# Arduino_FPGA_Top-Level_Interface.net
KiCad netlist of a schematic drawn in Altium Designer
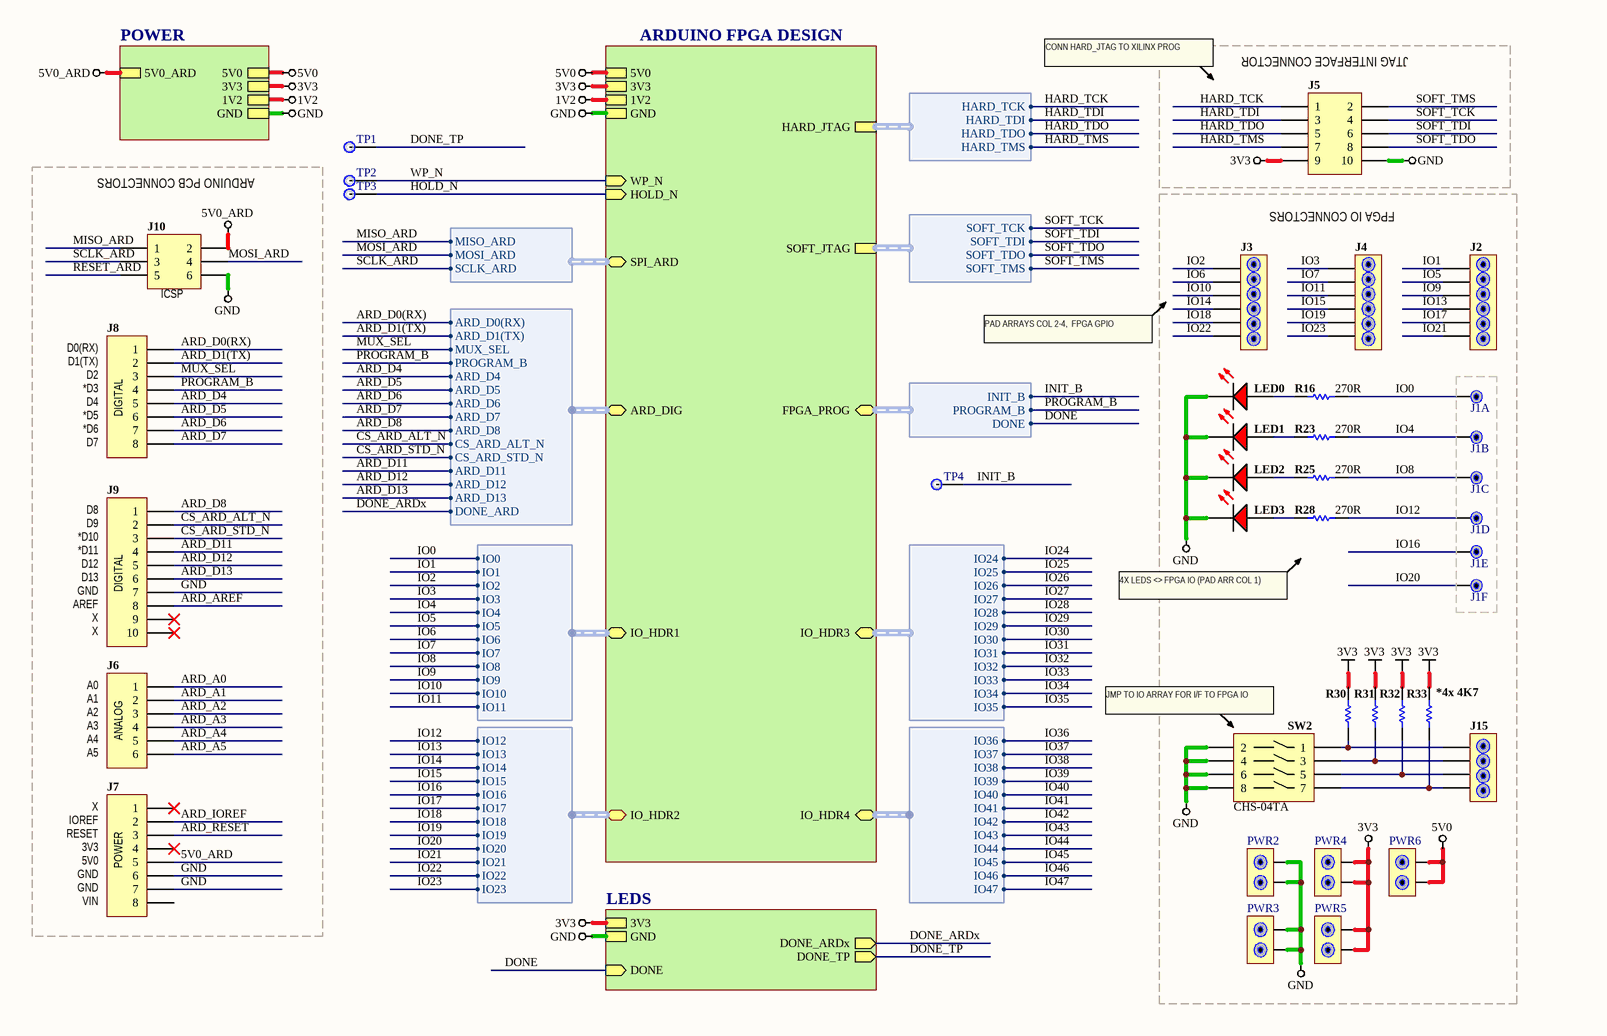
[diagram p0: Arduino FPGA Top-Level Interface.SchDoc]

(export (version "E")
  (design (tool "Eeschema 10.0.6"))
  (components
    (comp (ref "J1")
      (value "HDR1X6X1")
      (footprint "HDR1X6")
      (fields (field (name "MANUFACTURER PART NUMBER") "68000-406HLF"))
      (libsource (lib "HDR1") (part "HDR1X6X1"))
    )
    (comp (ref "J2")
      (value "6-POS VERTICAL HEADER")
      (footprint "HDR1X6")
      (fields (field (name "MANUFACTURER PART NUMBER") "68000-406HLF"))
      (libsource (lib "HDR1X6") (part "6-POS-HDR"))
    )
    (comp (ref "J3")
      (value "6-POS VERTICAL HEADER")
      (footprint "HDR1X6")
      (fields (field (name "MANUFACTURER PART NUMBER") "68000-406HLF"))
      (libsource (lib "HDR1X6") (part "6-POS-HDR"))
    )
    (comp (ref "J4")
      (value "6-POS VERTICAL HEADER")
      (footprint "HDR1X6")
      (fields (field (name "MANUFACTURER PART NUMBER") "68000-406HLF"))
      (libsource (lib "HDR1X6") (part "6-POS-HDR"))
    )
    (comp (ref "J5")
      (value "Header 5X2")
      (footprint "HDR2X5")
      (description "Header, 5-Pin, Dual row")
      (fields
        (field (name "MANUFACTURER PART NUMBER") "67997-210HLF")
        (field (name "PUBLISHER") "Altium Limited")
      )
      (libsource (lib "Miscellaneous Connectors") (part "Header 5X2"))
    )
    (comp (ref "J6")
      (value "Header 6")
      (footprint "1X06")
      (description "Header, 6-Pin")
      (fields (field (name "MANUFACTURER PART NUMBER") "DNP") (field (name "PUBLISHER") "Altium Limited"))
      (libsource (lib "Miscellaneous Connectors") (part "Header 6"))
    )
    (comp (ref "J7")
      (value "Header 8")
      (footprint "1X08")
      (description "Header, 8-Pin")
      (fields (field (name "MANUFACTURER PART NUMBER") "DNP") (field (name "PUBLISHER") "Altium Limited"))
      (libsource (lib "Miscellaneous Connectors") (part "Header 8"))
    )
    (comp (ref "J8")
      (value "Header 8")
      (footprint "1X08")
      (description "Header, 8-Pin")
      (fields (field (name "MANUFACTURER PART NUMBER") "DNP") (field (name "PUBLISHER") "Altium Limited"))
      (libsource (lib "Miscellaneous Connectors") (part "Header 8"))
    )
    (comp (ref "J9")
      (value "Header 10")
      (footprint "1X10@1")
      (description "Header, 10-Pin")
      (fields (field (name "MANUFACTURER PART NUMBER") "DNP") (field (name "PUBLISHER") "Altium Limited"))
      (libsource (lib "Miscellaneous Connectors") (part "Header 10"))
    )
    (comp (ref "J10")
      (value "Header 3X2")
      (footprint "2X03")
      (description "Header, 3-Pin, Dual row")
      (fields (field (name "MANUFACTURER PART NUMBER") "DNP") (field (name "PUBLISHER") "Altium Limited"))
      (libsource (lib "Miscellaneous Connectors") (part "Header 3X2"))
    )
    (comp (ref "J15")
      (value "4-POS VERTICAL HEADER")
      (footprint "HDR1X4")
      (fields (field (name "MANUFACTURER PART NUMBER") "68000-404HLF"))
      (libsource (lib "HDR4") (part "4-POS-HDR"))
    )
    (comp (ref "LED0")
      (value "0402-LED-RED")
      (footprint "LED_0402")
      (description "0402 LED,RED")
      (fields (field (name "MANUFACTURER PART NUMBER") "LTST-C190KRKT"))
      (libsource (lib "Component_DB") (part "LED_RED_A1K2-2"))
    )
    (comp (ref "LED1")
      (value "0402-LED-RED")
      (footprint "LED_0402")
      (description "0402 LED,RED")
      (fields (field (name "MANUFACTURER PART NUMBER") "LTST-C190KRKT"))
      (libsource (lib "Component_DB") (part "LED_RED_A1K2-2"))
    )
    (comp (ref "LED2")
      (value "0402-LED-RED")
      (footprint "LED_0402")
      (description "0402 LED,RED")
      (fields (field (name "MANUFACTURER PART NUMBER") "LTST-C190KRKT"))
      (libsource (lib "Component_DB") (part "LED_RED_A1K2-2"))
    )
    (comp (ref "LED3")
      (value "0402-LED-RED")
      (footprint "LED_0402")
      (description "0402 LED,RED")
      (fields (field (name "MANUFACTURER PART NUMBER") "LTST-C190KRKT"))
      (libsource (lib "Component_DB") (part "LED_RED_A1K2-2"))
    )
    (comp (ref "PWR2")
      (value "Jumper")
      (footprint "JMP1X2")
      (description "Standard 2 Pin Jumper, 100mil spacing")
      (fields (field (name "MANUFACTURER PART NUMBER") "M20-9770246"))
      (libsource (lib "JMP1X2") (part "JMP1X2"))
    )
    (comp (ref "PWR3")
      (value "Jumper")
      (footprint "JMP1X2")
      (description "Standard 2 Pin Jumper, 100mil spacing")
      (fields (field (name "MANUFACTURER PART NUMBER") "M20-9770246"))
      (libsource (lib "JMP1X2") (part "JMP1X2"))
    )
    (comp (ref "PWR4")
      (value "Jumper")
      (footprint "JMP1X2")
      (description "Standard 2 Pin Jumper, 100mil spacing")
      (fields (field (name "MANUFACTURER PART NUMBER") "M20-9770246"))
      (libsource (lib "JMP1X2") (part "JMP1X2"))
    )
    (comp (ref "PWR5")
      (value "Jumper")
      (footprint "JMP1X2")
      (description "Standard 2 Pin Jumper, 100mil spacing")
      (fields (field (name "MANUFACTURER PART NUMBER") "M20-9770246"))
      (libsource (lib "JMP1X2") (part "JMP1X2"))
    )
    (comp (ref "PWR6")
      (value "Jumper")
      (footprint "JMP1X2")
      (description "Standard 2 Pin Jumper, 100mil spacing")
      (fields (field (name "MANUFACTURER PART NUMBER") "M20-9770246"))
      (libsource (lib "JMP1X2") (part "JMP1X2"))
    )
    (comp (ref "R16")
      (value "270R")
      (footprint "RESC0402(1005)40_L")
      (description "0402 (1005 Metric) 1/16 W 270R 1 Thick Film Chip Resistor")
      (fields (field (name "POWER") "1/16 W") (field (name "MANUFACTURER PART NUMBER") "RC1005F271CS"))
      (libsource (lib "Component_DB") (part "RES"))
    )
    (comp (ref "R23")
      (value "270R")
      (footprint "RESC0402(1005)40_L")
      (description "0402 (1005 Metric) 1/16 W 270R 1 Thick Film Chip Resistor")
      (fields (field (name "POWER") "1/16 W") (field (name "MANUFACTURER PART NUMBER") "RC1005F271CS"))
      (libsource (lib "Component_DB") (part "RES"))
    )
    (comp (ref "R25")
      (value "270R")
      (footprint "RESC0402(1005)40_L")
      (description "0402 (1005 Metric) 1/16 W 270R 1 Thick Film Chip Resistor")
      (fields (field (name "POWER") "1/16 W") (field (name "MANUFACTURER PART NUMBER") "RC1005F271CS"))
      (libsource (lib "Component_DB") (part "RES"))
    )
    (comp (ref "R28")
      (value "270R")
      (footprint "RESC0402(1005)40_L")
      (description "0402 (1005 Metric) 1/16 W 270R 1 Thick Film Chip Resistor")
      (fields (field (name "POWER") "1/16 W") (field (name "MANUFACTURER PART NUMBER") "RC1005F271CS"))
      (libsource (lib "Component_DB") (part "RES"))
    )
    (comp (ref "R30")
      (value "4K7 1 0402")
      (footprint "RESC0402(1005)40_L")
      (fields
        (field (name "POWER") "1/16 W")
        (field (name "MANUFACTURER PART NUMBER") "CR0402-FX-4701GLFDKR-ND")
      )
      (libsource (lib "Component_Database") (part "RES"))
    )
    (comp (ref "R31")
      (value "4K7 1 0402")
      (footprint "RESC0402(1005)40_L")
      (fields
        (field (name "POWER") "1/16 W")
        (field (name "MANUFACTURER PART NUMBER") "CR0402-FX-4701GLFDKR-ND")
      )
      (libsource (lib "Component_Database") (part "RES"))
    )
    (comp (ref "R32")
      (value "4K7 1 0402")
      (footprint "RESC0402(1005)40_L")
      (fields
        (field (name "POWER") "1/16 W")
        (field (name "MANUFACTURER PART NUMBER") "CR0402-FX-4701GLFDKR-ND")
      )
      (libsource (lib "Component_Database") (part "RES"))
    )
    (comp (ref "R33")
      (value "4K7 1 0402")
      (footprint "RESC0402(1005)40_L")
      (fields
        (field (name "POWER") "1/16 W")
        (field (name "MANUFACTURER PART NUMBER") "CR0402-FX-4701GLFDKR-ND")
      )
      (libsource (lib "Component_Database") (part "RES"))
    )
    (comp (ref "SW2")
      (value "CHS-04TA")
      (footprint "CHS-04A1")
      (description "SWITCH DIP 4-POS SLIDE SMD 6V")
      (fields (field (name "MANUFACTURER") "Copal Electronics Inc"))
      (libsource (lib "CHS-04TA") (part "CHS-04TA"))
    )
    (comp (ref "TP1")
      (value "TESTPOINT_TH")
      (footprint "TESTPOINT_TH")
      (fields (field (name "MANUFACTURER PART NUMBER") "TESTPOINT"))
      (libsource (lib "TESTPOINT_TH") (part "TESTPOINT_TH"))
    )
    (comp (ref "TP2")
      (value "TESTPOINT_TH")
      (footprint "TESTPOINT_TH")
      (fields (field (name "MANUFACTURER PART NUMBER") "TESTPOINT"))
      (libsource (lib "TESTPOINT_TH") (part "TESTPOINT_TH"))
    )
    (comp (ref "TP3")
      (value "TESTPOINT_TH")
      (footprint "TESTPOINT_TH")
      (fields (field (name "MANUFACTURER PART NUMBER") "TESTPOINT"))
      (libsource (lib "TESTPOINT_TH") (part "TESTPOINT_TH"))
    )
    (comp (ref "TP4")
      (value "TESTPOINT_TH")
      (footprint "TESTPOINT_TH")
      (fields (field (name "MANUFACTURER PART NUMBER") "TESTPOINT"))
      (libsource (lib "TESTPOINT_TH") (part "TESTPOINT_TH"))
    )
  )
  (nets
    (net (code "10") (name "/ARD_A0") (class "Default")
      (node (ref "J6") (pin "1") (pinfunction "1_1") (pintype "passive"))
    )
    (net (code "11") (name "/ARD_A1") (class "Default")
      (node (ref "J6") (pin "2") (pinfunction "2_2") (pintype "passive"))
    )
    (net (code "12") (name "/ARD_A2") (class "Default")
      (node (ref "J6") (pin "3") (pinfunction "3_3") (pintype "passive"))
    )
    (net (code "13") (name "/ARD_A3") (class "Default")
      (node (ref "J6") (pin "4") (pinfunction "4_4") (pintype "passive"))
    )
    (net (code "14") (name "/ARD_A4") (class "Default")
      (node (ref "J6") (pin "5") (pinfunction "5_5") (pintype "passive"))
    )
    (net (code "15") (name "/ARD_A5") (class "Default")
      (node (ref "J6") (pin "6") (pinfunction "6_6") (pintype "passive"))
    )
    (net (code "16") (name "/ARD_AREF") (class "Default")
      (node (ref "J9") (pin "8") (pinfunction "8_8") (pintype "passive"))
    )
    (net (code "17") (name "/ARD_D0(RX)") (class "Default")
      (node (ref "J8") (pin "1") (pinfunction "1_1") (pintype "passive"))
    )
    (net (code "18") (name "/ARD_D1(TX)") (class "Default")
      (node (ref "J8") (pin "2") (pinfunction "2_2") (pintype "passive"))
    )
    (net (code "19") (name "/ARD_D4") (class "Default")
      (node (ref "J8") (pin "5") (pinfunction "5_5") (pintype "passive"))
    )
    (net (code "20") (name "/ARD_D5") (class "Default")
      (node (ref "J8") (pin "6") (pinfunction "6_6") (pintype "passive"))
    )
    (net (code "21") (name "/ARD_D6") (class "Default")
      (node (ref "J8") (pin "7") (pinfunction "7_7") (pintype "passive"))
    )
    (net (code "22") (name "/ARD_D7") (class "Default")
      (node (ref "J8") (pin "8") (pinfunction "8_8") (pintype "passive"))
    )
    (net (code "23") (name "/ARD_D8") (class "Default")
      (node (ref "J9") (pin "1") (pinfunction "1_1") (pintype "passive"))
    )
    (net (code "24") (name "/ARD_D11") (class "Default")
      (node (ref "J9") (pin "4") (pinfunction "4_4") (pintype "passive"))
    )
    (net (code "25") (name "/ARD_D12") (class "Default")
      (node (ref "J9") (pin "5") (pinfunction "5_5") (pintype "passive"))
    )
    (net (code "26") (name "/ARD_D13") (class "Default")
      (node (ref "J9") (pin "6") (pinfunction "6_6") (pintype "passive"))
    )
    (net (code "27") (name "/ARD_IOREF") (class "Default")
      (node (ref "J7") (pin "2") (pinfunction "2_2") (pintype "passive"))
    )
    (net (code "28") (name "/ARD_RESET") (class "Default")
      (node (ref "J7") (pin "3") (pinfunction "3_3") (pintype "passive"))
    )
    (net (code "29") (name "/CS_ARD_ALT_N") (class "Default")
      (node (ref "J9") (pin "2") (pinfunction "2_2") (pintype "passive"))
    )
    (net (code "30") (name "/CS_ARD_STD_N") (class "Default")
      (node (ref "J9") (pin "3") (pinfunction "3_3") (pintype "passive"))
    )
    (net (code "33") (name "/DONE_TP") (class "Default")
      (node (ref "TP1") (pin "1") (pinfunction "1_1") (pintype "passive"))
    )
    (net (code "34") (name "/HARD_TCK") (class "Default")
      (node (ref "J5") (pin "1") (pinfunction "1_1") (pintype "passive"))
    )
    (net (code "35") (name "/HARD_TDI") (class "Default")
      (node (ref "J5") (pin "3") (pinfunction "3_3") (pintype "passive"))
    )
    (net (code "36") (name "/HARD_TDO") (class "Default")
      (node (ref "J5") (pin "5") (pinfunction "5_5") (pintype "passive"))
    )
    (net (code "37") (name "/HARD_TMS") (class "Default")
      (node (ref "J5") (pin "7") (pinfunction "7_7") (pintype "passive"))
    )
    (net (code "38") (name "/HOLD_N") (class "Default")
      (node (ref "TP3") (pin "1") (pinfunction "1_1") (pintype "passive"))
    )
    (net (code "39") (name "/INIT_B") (class "Default")
      (node (ref "TP4") (pin "1") (pinfunction "1_1") (pintype "passive"))
    )
    (net (code "40") (name "/IO0") (class "Default")
      (node (ref "J1") (pin "1") (pinfunction "1_1") (pintype "passive"))
      (node (ref "R16") (pin "2") (pinfunction "2_2") (pintype "passive"))
    )
    (net (code "41") (name "/IO1") (class "Default")
      (node (ref "J2") (pin "1") (pinfunction "1_1") (pintype "passive"))
    )
    (net (code "42") (name "/IO2") (class "Default")
      (node (ref "J3") (pin "1") (pinfunction "1_1") (pintype "passive"))
    )
    (net (code "43") (name "/IO3") (class "Default")
      (node (ref "J4") (pin "1") (pinfunction "1_1") (pintype "passive"))
    )
    (net (code "44") (name "/IO4") (class "Default")
      (node (ref "J1") (pin "2") (pinfunction "2_2") (pintype "passive"))
      (node (ref "R23") (pin "2") (pinfunction "2_2") (pintype "passive"))
    )
    (net (code "45") (name "/IO5") (class "Default")
      (node (ref "J2") (pin "2") (pinfunction "2_2") (pintype "passive"))
    )
    (net (code "46") (name "/IO6") (class "Default")
      (node (ref "J3") (pin "2") (pinfunction "2_2") (pintype "passive"))
    )
    (net (code "47") (name "/IO7") (class "Default")
      (node (ref "J4") (pin "2") (pinfunction "2_2") (pintype "passive"))
    )
    (net (code "48") (name "/IO8") (class "Default")
      (node (ref "J1") (pin "3") (pinfunction "3_3") (pintype "passive"))
      (node (ref "R25") (pin "2") (pinfunction "2_2") (pintype "passive"))
    )
    (net (code "49") (name "/IO9") (class "Default")
      (node (ref "J2") (pin "3") (pinfunction "3_3") (pintype "passive"))
    )
    (net (code "50") (name "/IO10") (class "Default")
      (node (ref "J3") (pin "3") (pinfunction "3_3") (pintype "passive"))
    )
    (net (code "51") (name "/IO11") (class "Default")
      (node (ref "J4") (pin "3") (pinfunction "3_3") (pintype "passive"))
    )
    (net (code "52") (name "/IO12") (class "Default")
      (node (ref "J1") (pin "4") (pinfunction "4_4") (pintype "passive"))
      (node (ref "R28") (pin "2") (pinfunction "2_2") (pintype "passive"))
    )
    (net (code "53") (name "/IO13") (class "Default")
      (node (ref "J2") (pin "4") (pinfunction "4_4") (pintype "passive"))
    )
    (net (code "54") (name "/IO14") (class "Default")
      (node (ref "J3") (pin "4") (pinfunction "4_4") (pintype "passive"))
    )
    (net (code "55") (name "/IO15") (class "Default")
      (node (ref "J4") (pin "4") (pinfunction "4_4") (pintype "passive"))
    )
    (net (code "56") (name "/IO16") (class "Default")
      (node (ref "J1") (pin "5") (pinfunction "5_5") (pintype "passive"))
    )
    (net (code "57") (name "/IO17") (class "Default")
      (node (ref "J2") (pin "5") (pinfunction "5_5") (pintype "passive"))
    )
    (net (code "58") (name "/IO18") (class "Default")
      (node (ref "J3") (pin "5") (pinfunction "5_5") (pintype "passive"))
    )
    (net (code "59") (name "/IO19") (class "Default")
      (node (ref "J4") (pin "5") (pinfunction "5_5") (pintype "passive"))
    )
    (net (code "60") (name "/IO20") (class "Default")
      (node (ref "J1") (pin "6") (pinfunction "6_6") (pintype "passive"))
    )
    (net (code "61") (name "/IO21") (class "Default")
      (node (ref "J2") (pin "6") (pinfunction "6_6") (pintype "passive"))
    )
    (net (code "62") (name "/IO22") (class "Default")
      (node (ref "J3") (pin "6") (pinfunction "6_6") (pintype "passive"))
    )
    (net (code "63") (name "/IO23") (class "Default")
      (node (ref "J4") (pin "6") (pinfunction "6_6") (pintype "passive"))
    )
    (net (code "88") (name "/MISO_ARD") (class "Default")
      (node (ref "J10") (pin "1") (pinfunction "1_1") (pintype "passive"))
    )
    (net (code "89") (name "/MOSI_ARD") (class "Default")
      (node (ref "J10") (pin "4") (pinfunction "4_4") (pintype "passive"))
    )
    (net (code "90") (name "/MUX_SEL") (class "Default")
      (node (ref "J8") (pin "3") (pinfunction "3_3") (pintype "passive"))
    )
    (net (code "91") (name "/PROGRAM_B") (class "Default")
      (node (ref "J8") (pin "4") (pinfunction "4_4") (pintype "passive"))
    )
    (net (code "92") (name "/RESET_ARD") (class "Default")
      (node (ref "J10") (pin "5") (pinfunction "5_5") (pintype "passive"))
    )
    (net (code "93") (name "/SCLK_ARD") (class "Default")
      (node (ref "J10") (pin "3") (pinfunction "3_3") (pintype "passive"))
    )
    (net (code "94") (name "/SOFT_TCK") (class "Default")
      (node (ref "J5") (pin "4") (pinfunction "4_4") (pintype "passive"))
    )
    (net (code "95") (name "/SOFT_TDI") (class "Default")
      (node (ref "J5") (pin "6") (pinfunction "6_6") (pintype "passive"))
    )
    (net (code "96") (name "/SOFT_TDO") (class "Default")
      (node (ref "J5") (pin "8") (pinfunction "8_8") (pintype "passive"))
    )
    (net (code "97") (name "/SOFT_TMS") (class "Default")
      (node (ref "J5") (pin "2") (pinfunction "2_2") (pintype "passive"))
    )
    (net (code "98") (name "/WP_N") (class "Default")
      (node (ref "TP2") (pin "1") (pinfunction "1_1") (pintype "passive"))
    )
    (net (code "109") (name "3V3") (class "Default")
      (node (ref "J5") (pin "9") (pinfunction "9_9") (pintype "passive"))
      (node (ref "PWR4") (pin "1") (pinfunction "1_1") (pintype "passive"))
      (node (ref "PWR4") (pin "2") (pinfunction "2_2") (pintype "passive"))
      (node (ref "PWR5") (pin "1") (pinfunction "1_1") (pintype "passive"))
      (node (ref "PWR5") (pin "2") (pinfunction "2_2") (pintype "passive"))
      (node (ref "R30") (pin "2") (pinfunction "2_2") (pintype "passive"))
      (node (ref "R31") (pin "2") (pinfunction "2_2") (pintype "passive"))
      (node (ref "R32") (pin "2") (pinfunction "2_2") (pintype "passive"))
      (node (ref "R33") (pin "2") (pinfunction "2_2") (pintype "passive"))
    )
    (net (code "110") (name "5V0") (class "Default")
      (node (ref "PWR6") (pin "1") (pinfunction "1_1") (pintype "passive"))
      (node (ref "PWR6") (pin "2") (pinfunction "2_2") (pintype "passive"))
    )
    (net (code "111") (name "5V0_ARD") (class "Default")
      (node (ref "J7") (pin "5") (pinfunction "5_5") (pintype "passive"))
    )
    (net (code "112") (name "GND") (class "Default")
      (node (ref "J10") (pin "6") (pinfunction "6_6") (pintype "passive"))
      (node (ref "J5") (pin "10") (pinfunction "10_10") (pintype "passive"))
      (node (ref "J7") (pin "6") (pinfunction "6_6") (pintype "passive"))
      (node (ref "J7") (pin "7") (pinfunction "7_7") (pintype "passive"))
      (node (ref "J9") (pin "7") (pinfunction "7_7") (pintype "passive"))
      (node (ref "LED0") (pin "2") (pinfunction "K_2") (pintype "passive"))
      (node (ref "LED1") (pin "2") (pinfunction "K_2") (pintype "passive"))
      (node (ref "LED2") (pin "2") (pinfunction "K_2") (pintype "passive"))
      (node (ref "LED3") (pin "2") (pinfunction "K_2") (pintype "passive"))
      (node (ref "PWR2") (pin "1") (pinfunction "1_1") (pintype "passive"))
      (node (ref "PWR2") (pin "2") (pinfunction "2_2") (pintype "passive"))
      (node (ref "PWR3") (pin "1") (pinfunction "1_1") (pintype "passive"))
      (node (ref "PWR3") (pin "2") (pinfunction "2_2") (pintype "passive"))
      (node (ref "SW2") (pin "2") (pinfunction "2_2") (pintype "passive"))
      (node (ref "SW2") (pin "4") (pinfunction "4_4") (pintype "passive"))
      (node (ref "SW2") (pin "6") (pinfunction "6_6") (pintype "passive"))
      (node (ref "SW2") (pin "8") (pinfunction "8_8") (pintype "passive"))
    )
    (net (code "113") (name "Net-(J15-Pad1)") (class "Default")
      (node (ref "J15") (pin "1") (pinfunction "1_1") (pintype "passive"))
      (node (ref "R30") (pin "1") (pinfunction "1_1") (pintype "passive"))
      (node (ref "SW2") (pin "1") (pinfunction "1_1") (pintype "passive"))
    )
    (net (code "114") (name "Net-(J15-Pad2)") (class "Default")
      (node (ref "J15") (pin "2") (pinfunction "2_2") (pintype "passive"))
      (node (ref "R31") (pin "1") (pinfunction "1_1") (pintype "passive"))
      (node (ref "SW2") (pin "3") (pinfunction "3_3") (pintype "passive"))
    )
    (net (code "115") (name "Net-(J15-Pad3)") (class "Default")
      (node (ref "J15") (pin "3") (pinfunction "3_3") (pintype "passive"))
      (node (ref "R32") (pin "1") (pinfunction "1_1") (pintype "passive"))
      (node (ref "SW2") (pin "5") (pinfunction "5_5") (pintype "passive"))
    )
    (net (code "116") (name "Net-(J15-Pad4)") (class "Default")
      (node (ref "J15") (pin "4") (pinfunction "4_4") (pintype "passive"))
      (node (ref "R33") (pin "1") (pinfunction "1_1") (pintype "passive"))
      (node (ref "SW2") (pin "7") (pinfunction "7_7") (pintype "passive"))
    )
    (net (code "117") (name "Net-(LED0-A)") (class "Default")
      (node (ref "LED0") (pin "1") (pinfunction "A_1") (pintype "passive"))
      (node (ref "R16") (pin "1") (pinfunction "1_1") (pintype "passive"))
    )
    (net (code "118") (name "Net-(LED1-A)") (class "Default")
      (node (ref "LED1") (pin "1") (pinfunction "A_1") (pintype "passive"))
      (node (ref "R23") (pin "1") (pinfunction "1_1") (pintype "passive"))
    )
    (net (code "119") (name "Net-(LED2-A)") (class "Default")
      (node (ref "LED2") (pin "1") (pinfunction "A_1") (pintype "passive"))
      (node (ref "R25") (pin "1") (pinfunction "1_1") (pintype "passive"))
    )
    (net (code "120") (name "Net-(LED3-A)") (class "Default")
      (node (ref "LED3") (pin "1") (pinfunction "A_1") (pintype "passive"))
      (node (ref "R28") (pin "1") (pinfunction "1_1") (pintype "passive"))
    )
    (net (code "121") (name "unconnected-(J7-Pad1)") (class "Default")
      (node (ref "J7") (pin "1") (pinfunction "1_1") (pintype "passive+no_connect"))
    )
    (net (code "122") (name "unconnected-(J7-Pad4)") (class "Default")
      (node (ref "J7") (pin "4") (pinfunction "4_4") (pintype "passive+no_connect"))
    )
    (net (code "123") (name "unconnected-(J7-Pad8)") (class "Default")
      (node (ref "J7") (pin "8") (pinfunction "8_8") (pintype "passive"))
    )
    (net (code "124") (name "unconnected-(J9-Pad9)") (class "Default")
      (node (ref "J9") (pin "9") (pinfunction "9_9") (pintype "passive+no_connect"))
    )
    (net (code "125") (name "unconnected-(J9-Pad10)") (class "Default")
      (node (ref "J9") (pin "10") (pinfunction "10_10") (pintype "passive+no_connect"))
    )
    (net (code "126") (name "unconnected-(J10-Pad2)") (class "Default")
      (node (ref "J10") (pin "2") (pinfunction "2_2") (pintype "passive"))
    )
  )
)
